# Reset.net
KiCad netlist of a schematic drawn in Altium Designer
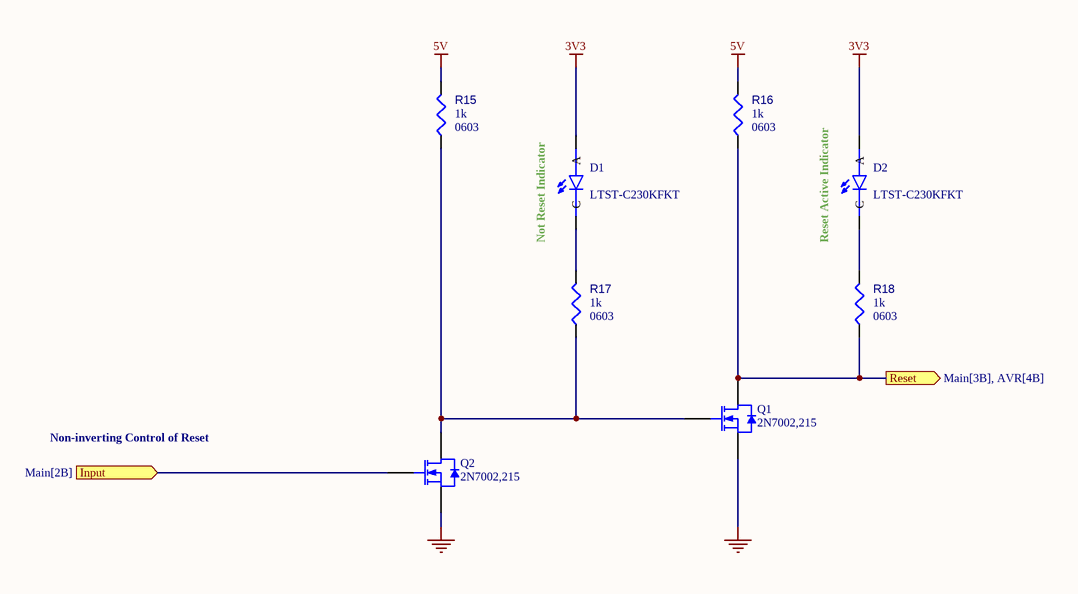
[diagram p0: Reset.SchDoc]

(export (version "E")
  (design (tool "Eeschema 10.0.6"))
  (components
    (comp (ref "D1")
      (value "LTST-C230KFKT")
      (footprint "LEDC3216X110")
      (description "Orange 605nm LED Indication - Discrete 2V 1206 (3216 Metric)")
      (fields (field (name "MF") "Lite-On Inc."))
      (libsource (lib "Twill Technology Inc") (part "LTST-C230KFKT"))
    )
    (comp (ref "D2")
      (value "LTST-C230KFKT")
      (footprint "LEDC3216X110")
      (description "Orange 605nm LED Indication - Discrete 2V 1206 (3216 Metric)")
      (fields (field (name "MF") "Lite-On Inc."))
      (libsource (lib "Twill Technology Inc") (part "LTST-C230KFKT"))
    )
    (comp (ref "Q1")
      (value "2N7002,215")
      (footprint "NXP-SOT23-3_V")
      (fields (field (name "POWER") "830mW") (field (name "MANUFACTURER") "NXP Semiconductors"))
      (libsource (lib "Twill Technology Inc") (part "NEMOS-GSD-3"))
    )
    (comp (ref "Q2")
      (value "2N7002,215")
      (footprint "NXP-SOT23-3_V")
      (fields (field (name "POWER") "830mW") (field (name "MANUFACTURER") "NXP Semiconductors"))
      (libsource (lib "Twill Technology Inc") (part "NEMOS-GSD-3"))
    )
    (comp (ref "R15")
      (value "1k")
      (footprint "RESC1608X55X25ML10T15")
      (description "Chip Resistor, 1 KOhm, +/-1%, 0.1 W, -55 to 155 degC, 0603 (1608 Metric)")
      (fields
        (field (name "CASE/PACKAGE") "0603")
        (field (name "POWER") "100mW")
        (field (name "TOLERANCE") "1%")
      )
      (libsource (lib "Twill Technology Inc") (part "RES-2"))
    )
    (comp (ref "R16")
      (value "1k")
      (footprint "RESC1608X55X25ML10T15")
      (description "Chip Resistor, 1 KOhm, +/-1%, 0.1 W, -55 to 155 degC, 0603 (1608 Metric)")
      (fields
        (field (name "CASE/PACKAGE") "0603")
        (field (name "POWER") "100mW")
        (field (name "TOLERANCE") "1%")
      )
      (libsource (lib "Twill Technology Inc") (part "RES-2"))
    )
    (comp (ref "R17")
      (value "1k")
      (footprint "RESC1608X55X25ML10T15")
      (description "Chip Resistor, 1 KOhm, +/-1%, 0.1 W, -55 to 155 degC, 0603 (1608 Metric)")
      (fields
        (field (name "CASE/PACKAGE") "0603")
        (field (name "POWER") "100mW")
        (field (name "TOLERANCE") "1%")
      )
      (libsource (lib "Twill Technology Inc") (part "RES-2"))
    )
    (comp (ref "R18")
      (value "1k")
      (footprint "RESC1608X55X25ML10T15")
      (description "Chip Resistor, 1 KOhm, +/-1%, 0.1 W, -55 to 155 degC, 0603 (1608 Metric)")
      (fields
        (field (name "CASE/PACKAGE") "0603")
        (field (name "POWER") "100mW")
        (field (name "TOLERANCE") "1%")
      )
      (libsource (lib "Twill Technology Inc") (part "RES-2"))
    )
  )
  (nets
    (net (code "1") (name "/Input") (class "Default")
      (node (ref "Q2") (pin "1") (pinfunction "G_1") (pintype "passive"))
    )
    (net (code "2") (name "/Reset") (class "Default")
      (node (ref "Q1") (pin "3") (pinfunction "D_3") (pintype "passive"))
      (node (ref "R16") (pin "1") (pinfunction "1_1") (pintype "passive"))
      (node (ref "R18") (pin "1") (pinfunction "1_1") (pintype "passive"))
    )
    (net (code "3") (name "3V3") (class "Default")
      (node (ref "D1") (pin "A") (pinfunction "A_A") (pintype "passive"))
      (node (ref "D2") (pin "A") (pinfunction "A_A") (pintype "passive"))
    )
    (net (code "4") (name "5V") (class "Default")
      (node (ref "R15") (pin "2") (pinfunction "2_2") (pintype "passive"))
      (node (ref "R16") (pin "2") (pinfunction "2_2") (pintype "passive"))
    )
    (net (code "5") (name "GND") (class "Default")
      (node (ref "Q1") (pin "2") (pinfunction "S_2") (pintype "passive"))
      (node (ref "Q2") (pin "2") (pinfunction "S_2") (pintype "passive"))
    )
    (net (code "6") (name "Net-(D1-PadC)") (class "Default")
      (node (ref "D1") (pin "C") (pinfunction "C_C") (pintype "passive"))
      (node (ref "R17") (pin "2") (pinfunction "2_2") (pintype "passive"))
    )
    (net (code "7") (name "Net-(D2-PadC)") (class "Default")
      (node (ref "D2") (pin "C") (pinfunction "C_C") (pintype "passive"))
      (node (ref "R18") (pin "2") (pinfunction "2_2") (pintype "passive"))
    )
    (net (code "8") (name "Net-(Q1-G)") (class "Default")
      (node (ref "Q1") (pin "1") (pinfunction "G_1") (pintype "passive"))
      (node (ref "Q2") (pin "3") (pinfunction "D_3") (pintype "passive"))
      (node (ref "R15") (pin "1") (pinfunction "1_1") (pintype "passive"))
      (node (ref "R17") (pin "1") (pinfunction "1_1") (pintype "passive"))
    )
  )
)
